# usb_to_full_duplex_rs485.net
KiCad netlist of a schematic drawn in Altium Designer
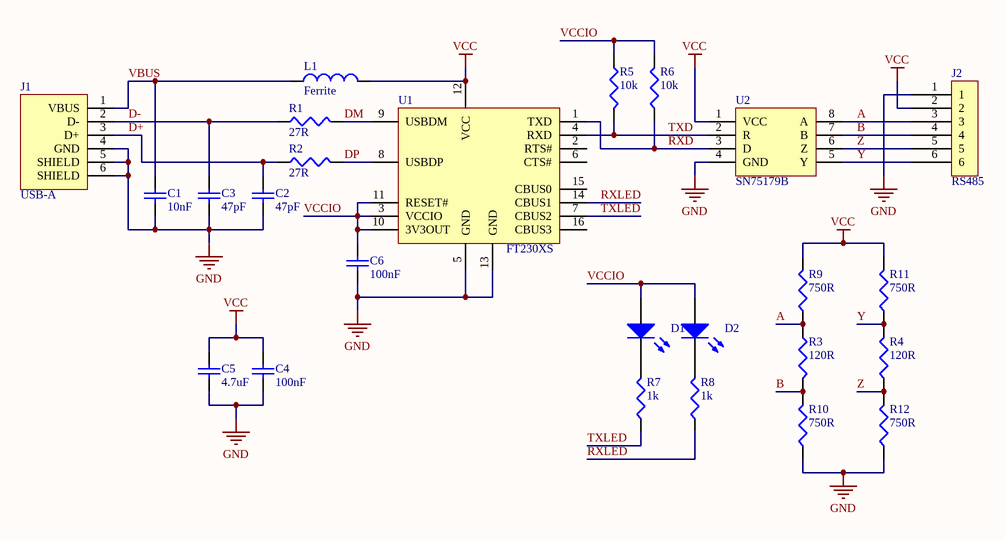
[diagram p0: usb_to_full_duplex_rs485.SchDoc]

(export (version "E")
  (design (tool "Eeschema 10.0.6"))
  (components
    (comp (ref "C1")
      (value "10nF")
      (footprint "1608[0603]")
      (description "Capacitor (Semiconductor SIM Model)")
      (fields (field (name "PUBLISHER") "Altium Limited"))
      (libsource (lib "Miscellaneous Devices") (part "Cap Semi"))
    )
    (comp (ref "C2")
      (value "47pF")
      (footprint "1608[0603]")
      (description "Capacitor (Semiconductor SIM Model)")
      (fields (field (name "PUBLISHER") "Altium Limited"))
      (libsource (lib "Miscellaneous Devices") (part "Cap Semi"))
    )
    (comp (ref "C3")
      (value "47pF")
      (footprint "1608[0603]")
      (description "Capacitor (Semiconductor SIM Model)")
      (fields (field (name "PUBLISHER") "Altium Limited"))
      (libsource (lib "Miscellaneous Devices") (part "Cap Semi"))
    )
    (comp (ref "C4")
      (value "100nF")
      (footprint "1608[0603]")
      (description "Capacitor (Semiconductor SIM Model)")
      (fields (field (name "PUBLISHER") "Altium Limited"))
      (libsource (lib "Miscellaneous Devices") (part "Cap Semi"))
    )
    (comp (ref "C5")
      (value "4.7uF")
      (footprint "1608[0603]")
      (description "Capacitor (Semiconductor SIM Model)")
      (fields (field (name "PUBLISHER") "Altium Limited"))
      (libsource (lib "Miscellaneous Devices") (part "Cap Semi"))
    )
    (comp (ref "C6")
      (value "100nF")
      (footprint "1608[0603]")
      (description "Capacitor (Semiconductor SIM Model)")
      (fields (field (name "PUBLISHER") "Altium Limited"))
      (libsource (lib "Miscellaneous Devices") (part "Cap Semi"))
    )
    (comp (ref "D1")
      (value "LED2")
      (footprint "1608[0603]")
      (description "Typical RED, GREEN, YELLOW, AMBER GaAs LED")
      (fields (field (name "PUBLISHER") "Altium Limited"))
      (libsource (lib "Miscellaneous Devices") (part "LED2"))
    )
    (comp (ref "D2")
      (value "LED2")
      (footprint "1608[0603]")
      (description "Typical RED, GREEN, YELLOW, AMBER GaAs LED")
      (fields (field (name "PUBLISHER") "Altium Limited"))
      (libsource (lib "Miscellaneous Devices") (part "LED2"))
    )
    (comp (ref "J1") (value "USB-A") (footprint "USB-A-PLUG") (libsource (lib "connectors") (part "USB-A")))
    (comp (ref "J2")
      (value "RS485")
      (footprint "MICRO-MATCH-6")
      (libsource (lib "connectors") (part "HEADER-6"))
    )
    (comp (ref "L1")
      (value "Ferrite")
      (footprint "INDC1608L")
      (fields (field (name "PUBLISHER") "Altium Limited"))
      (libsource (lib "Miscellaneous Devices") (part "Inductor"))
    )
    (comp (ref "R1")
      (value "27R")
      (footprint "J1-0603")
      (description "Resistor")
      (fields (field (name "PUBLISHER") "Altium Limited"))
      (libsource (lib "Miscellaneous Devices") (part "Res3"))
    )
    (comp (ref "R2")
      (value "27R")
      (footprint "J1-0603")
      (description "Resistor")
      (fields (field (name "PUBLISHER") "Altium Limited"))
      (libsource (lib "Miscellaneous Devices") (part "Res3"))
    )
    (comp (ref "R3")
      (value "120R")
      (footprint "J1-0603")
      (description "Resistor")
      (fields (field (name "PUBLISHER") "Altium Limited"))
      (libsource (lib "Miscellaneous Devices") (part "Res3"))
    )
    (comp (ref "R4")
      (value "120R")
      (footprint "J1-0603")
      (description "Resistor")
      (fields (field (name "PUBLISHER") "Altium Limited"))
      (libsource (lib "Miscellaneous Devices") (part "Res3"))
    )
    (comp (ref "R5")
      (value "10k")
      (footprint "J1-0603")
      (description "Resistor")
      (fields (field (name "PUBLISHER") "Altium Limited"))
      (libsource (lib "Miscellaneous Devices") (part "Res3"))
    )
    (comp (ref "R6")
      (value "10k")
      (footprint "J1-0603")
      (description "Resistor")
      (fields (field (name "PUBLISHER") "Altium Limited"))
      (libsource (lib "Miscellaneous Devices") (part "Res3"))
    )
    (comp (ref "R7")
      (value "1k")
      (footprint "J1-0603")
      (description "Resistor")
      (fields (field (name "PUBLISHER") "Altium Limited"))
      (libsource (lib "Miscellaneous Devices") (part "Res3"))
    )
    (comp (ref "R8")
      (value "1k")
      (footprint "J1-0603")
      (description "Resistor")
      (fields (field (name "PUBLISHER") "Altium Limited"))
      (libsource (lib "Miscellaneous Devices") (part "Res3"))
    )
    (comp (ref "R9")
      (value "750R")
      (footprint "J1-0603")
      (description "Resistor")
      (fields (field (name "PUBLISHER") "Altium Limited"))
      (libsource (lib "Miscellaneous Devices") (part "Res3"))
    )
    (comp (ref "R10")
      (value "750R")
      (footprint "J1-0603")
      (description "Resistor")
      (fields (field (name "PUBLISHER") "Altium Limited"))
      (libsource (lib "Miscellaneous Devices") (part "Res3"))
    )
    (comp (ref "R11")
      (value "750R")
      (footprint "J1-0603")
      (description "Resistor")
      (fields (field (name "PUBLISHER") "Altium Limited"))
      (libsource (lib "Miscellaneous Devices") (part "Res3"))
    )
    (comp (ref "R12")
      (value "750R")
      (footprint "J1-0603")
      (description "Resistor")
      (fields (field (name "PUBLISHER") "Altium Limited"))
      (libsource (lib "Miscellaneous Devices") (part "Res3"))
    )
    (comp (ref "U1")
      (value "FT230XS")
      (footprint "SOP64P600X175-16N")
      (libsource (lib "ftdi_chip") (part "FT230XS"))
    )
    (comp (ref "U2")
      (value "SN75179B")
      (footprint "SOIC-8")
      (libsource (lib "texas_instruments") (part "SN75179B"))
    )
  )
  (nets
    (net (code "1") (name "/A") (class "Default")
      (node (ref "J2") (pin "3") (pinfunction "3_3") (pintype "passive"))
      (node (ref "R3") (pin "1") (pinfunction "1_1") (pintype "passive"))
      (node (ref "R9") (pin "1") (pinfunction "1_1") (pintype "passive"))
      (node (ref "U2") (pin "8") (pinfunction "A_8") (pintype "passive"))
    )
    (net (code "2") (name "/B") (class "Default")
      (node (ref "J2") (pin "4") (pinfunction "4_4") (pintype "passive"))
      (node (ref "R10") (pin "2") (pinfunction "2_2") (pintype "passive"))
      (node (ref "R3") (pin "2") (pinfunction "2_2") (pintype "passive"))
      (node (ref "U2") (pin "7") (pinfunction "B_7") (pintype "passive"))
    )
    (net (code "3") (name "/D+") (class "Default")
      (node (ref "C2") (pin "2") (pinfunction "2_2") (pintype "passive"))
      (node (ref "J1") (pin "3") (pinfunction "D+_3") (pintype "passive"))
      (node (ref "R2") (pin "1") (pinfunction "1_1") (pintype "passive"))
    )
    (net (code "4") (name "/D-") (class "Default")
      (node (ref "C3") (pin "1") (pinfunction "1_1") (pintype "passive"))
      (node (ref "J1") (pin "2") (pinfunction "D-_2") (pintype "passive"))
      (node (ref "R1") (pin "1") (pinfunction "1_1") (pintype "passive"))
    )
    (net (code "5") (name "/DM") (class "Default")
      (node (ref "R1") (pin "2") (pinfunction "2_2") (pintype "passive"))
      (node (ref "U1") (pin "9") (pinfunction "USBDM_9") (pintype "passive"))
    )
    (net (code "6") (name "/DP") (class "Default")
      (node (ref "R2") (pin "2") (pinfunction "2_2") (pintype "passive"))
      (node (ref "U1") (pin "8") (pinfunction "USBDP_8") (pintype "passive"))
    )
    (net (code "7") (name "/RXD") (class "Default")
      (node (ref "R6") (pin "1") (pinfunction "1_1") (pintype "passive"))
      (node (ref "U1") (pin "1") (pinfunction "TXD_1") (pintype "passive"))
      (node (ref "U2") (pin "3") (pinfunction "D_3") (pintype "passive"))
    )
    (net (code "8") (name "/RXLED") (class "Default")
      (node (ref "R8") (pin "1") (pinfunction "1_1") (pintype "passive"))
      (node (ref "U1") (pin "14") (pinfunction "CBUS1_14") (pintype "passive"))
    )
    (net (code "9") (name "/TXD") (class "Default")
      (node (ref "R5") (pin "2") (pinfunction "2_2") (pintype "passive"))
      (node (ref "U1") (pin "4") (pinfunction "RXD_4") (pintype "passive"))
      (node (ref "U2") (pin "2") (pinfunction "R_2") (pintype "passive"))
    )
    (net (code "10") (name "/TXLED") (class "Default")
      (node (ref "R7") (pin "1") (pinfunction "1_1") (pintype "passive"))
      (node (ref "U1") (pin "7") (pinfunction "CBUS2_7") (pintype "passive"))
    )
    (net (code "11") (name "/VBUS") (class "Default")
      (node (ref "C1") (pin "1") (pinfunction "1_1") (pintype "passive"))
      (node (ref "J1") (pin "1") (pinfunction "VBUS_1") (pintype "passive"))
      (node (ref "L1") (pin "1") (pinfunction "1_1") (pintype "passive"))
    )
    (net (code "12") (name "/VCCIO") (class "Default")
      (node (ref "C6") (pin "2") (pinfunction "2_2") (pintype "passive"))
      (node (ref "D1") (pin "1") (pinfunction "A_1") (pintype "passive"))
      (node (ref "D2") (pin "1") (pinfunction "A_1") (pintype "passive"))
      (node (ref "R5") (pin "1") (pinfunction "1_1") (pintype "passive"))
      (node (ref "R6") (pin "2") (pinfunction "2_2") (pintype "passive"))
      (node (ref "U1") (pin "10") (pinfunction "3V3OUT_10") (pintype "passive"))
      (node (ref "U1") (pin "11") (pinfunction "RESET#_11") (pintype "passive"))
      (node (ref "U1") (pin "3") (pinfunction "VCCIO_3") (pintype "passive"))
    )
    (net (code "13") (name "/Y") (class "Default")
      (node (ref "J2") (pin "6") (pinfunction "6_6") (pintype "passive"))
      (node (ref "R11") (pin "1") (pinfunction "1_1") (pintype "passive"))
      (node (ref "R4") (pin "2") (pinfunction "2_2") (pintype "passive"))
      (node (ref "U2") (pin "5") (pinfunction "Y_5") (pintype "passive"))
    )
    (net (code "14") (name "/Z") (class "Default")
      (node (ref "J2") (pin "5") (pinfunction "5_5") (pintype "passive"))
      (node (ref "R12") (pin "2") (pinfunction "2_2") (pintype "passive"))
      (node (ref "R4") (pin "1") (pinfunction "1_1") (pintype "passive"))
      (node (ref "U2") (pin "6") (pinfunction "Z_6") (pintype "passive"))
    )
    (net (code "15") (name "GND") (class "Default")
      (node (ref "C1") (pin "2") (pinfunction "2_2") (pintype "passive"))
      (node (ref "C2") (pin "1") (pinfunction "1_1") (pintype "passive"))
      (node (ref "C3") (pin "2") (pinfunction "2_2") (pintype "passive"))
      (node (ref "C4") (pin "2") (pinfunction "2_2") (pintype "passive"))
      (node (ref "C5") (pin "1") (pinfunction "1_1") (pintype "passive"))
      (node (ref "C6") (pin "1") (pinfunction "1_1") (pintype "passive"))
      (node (ref "J1") (pin "4") (pinfunction "GND_4") (pintype "passive"))
      (node (ref "J1") (pin "5") (pinfunction "SHIELD_5") (pintype "passive"))
      (node (ref "J1") (pin "6") (pinfunction "SHIELD_6") (pintype "passive"))
      (node (ref "J2") (pin "1") (pinfunction "1_1") (pintype "passive"))
      (node (ref "R10") (pin "1") (pinfunction "1_1") (pintype "passive"))
      (node (ref "R12") (pin "1") (pinfunction "1_1") (pintype "passive"))
      (node (ref "U1") (pin "13") (pinfunction "GND_13") (pintype "passive"))
      (node (ref "U1") (pin "5") (pinfunction "GND_5") (pintype "passive"))
      (node (ref "U2") (pin "4") (pinfunction "GND_4") (pintype "passive"))
    )
    (net (code "16") (name "Net-(D1-K)") (class "Default")
      (node (ref "D1") (pin "2") (pinfunction "K_2") (pintype "passive"))
      (node (ref "R7") (pin "2") (pinfunction "2_2") (pintype "passive"))
    )
    (net (code "17") (name "Net-(D2-K)") (class "Default")
      (node (ref "D2") (pin "2") (pinfunction "K_2") (pintype "passive"))
      (node (ref "R8") (pin "2") (pinfunction "2_2") (pintype "passive"))
    )
    (net (code "18") (name "VCC") (class "Default")
      (node (ref "C4") (pin "1") (pinfunction "1_1") (pintype "passive"))
      (node (ref "C5") (pin "2") (pinfunction "2_2") (pintype "passive"))
      (node (ref "J2") (pin "2") (pinfunction "2_2") (pintype "passive"))
      (node (ref "L1") (pin "2") (pinfunction "2_2") (pintype "passive"))
      (node (ref "R11") (pin "2") (pinfunction "2_2") (pintype "passive"))
      (node (ref "R9") (pin "2") (pinfunction "2_2") (pintype "passive"))
      (node (ref "U1") (pin "12") (pinfunction "VCC_12") (pintype "passive"))
      (node (ref "U2") (pin "1") (pinfunction "VCC_1") (pintype "passive"))
    )
    (net (code "19") (name "unconnected-(U1-CBUS0-Pad15)") (class "Default")
      (node (ref "U1") (pin "15") (pinfunction "CBUS0_15") (pintype "passive"))
    )
    (net (code "20") (name "unconnected-(U1-CBUS3-Pad16)") (class "Default")
      (node (ref "U1") (pin "16") (pinfunction "CBUS3_16") (pintype "passive"))
    )
    (net (code "21") (name "unconnected-(U1-CTS#-Pad6)") (class "Default")
      (node (ref "U1") (pin "6") (pinfunction "CTS#_6") (pintype "passive"))
    )
    (net (code "22") (name "unconnected-(U1-RTS#-Pad2)") (class "Default")
      (node (ref "U1") (pin "2") (pinfunction "RTS#_2") (pintype "passive"))
    )
  )
)
